# WiFi_Board_R0.net
KiCad netlist of a schematic drawn in EAGLE
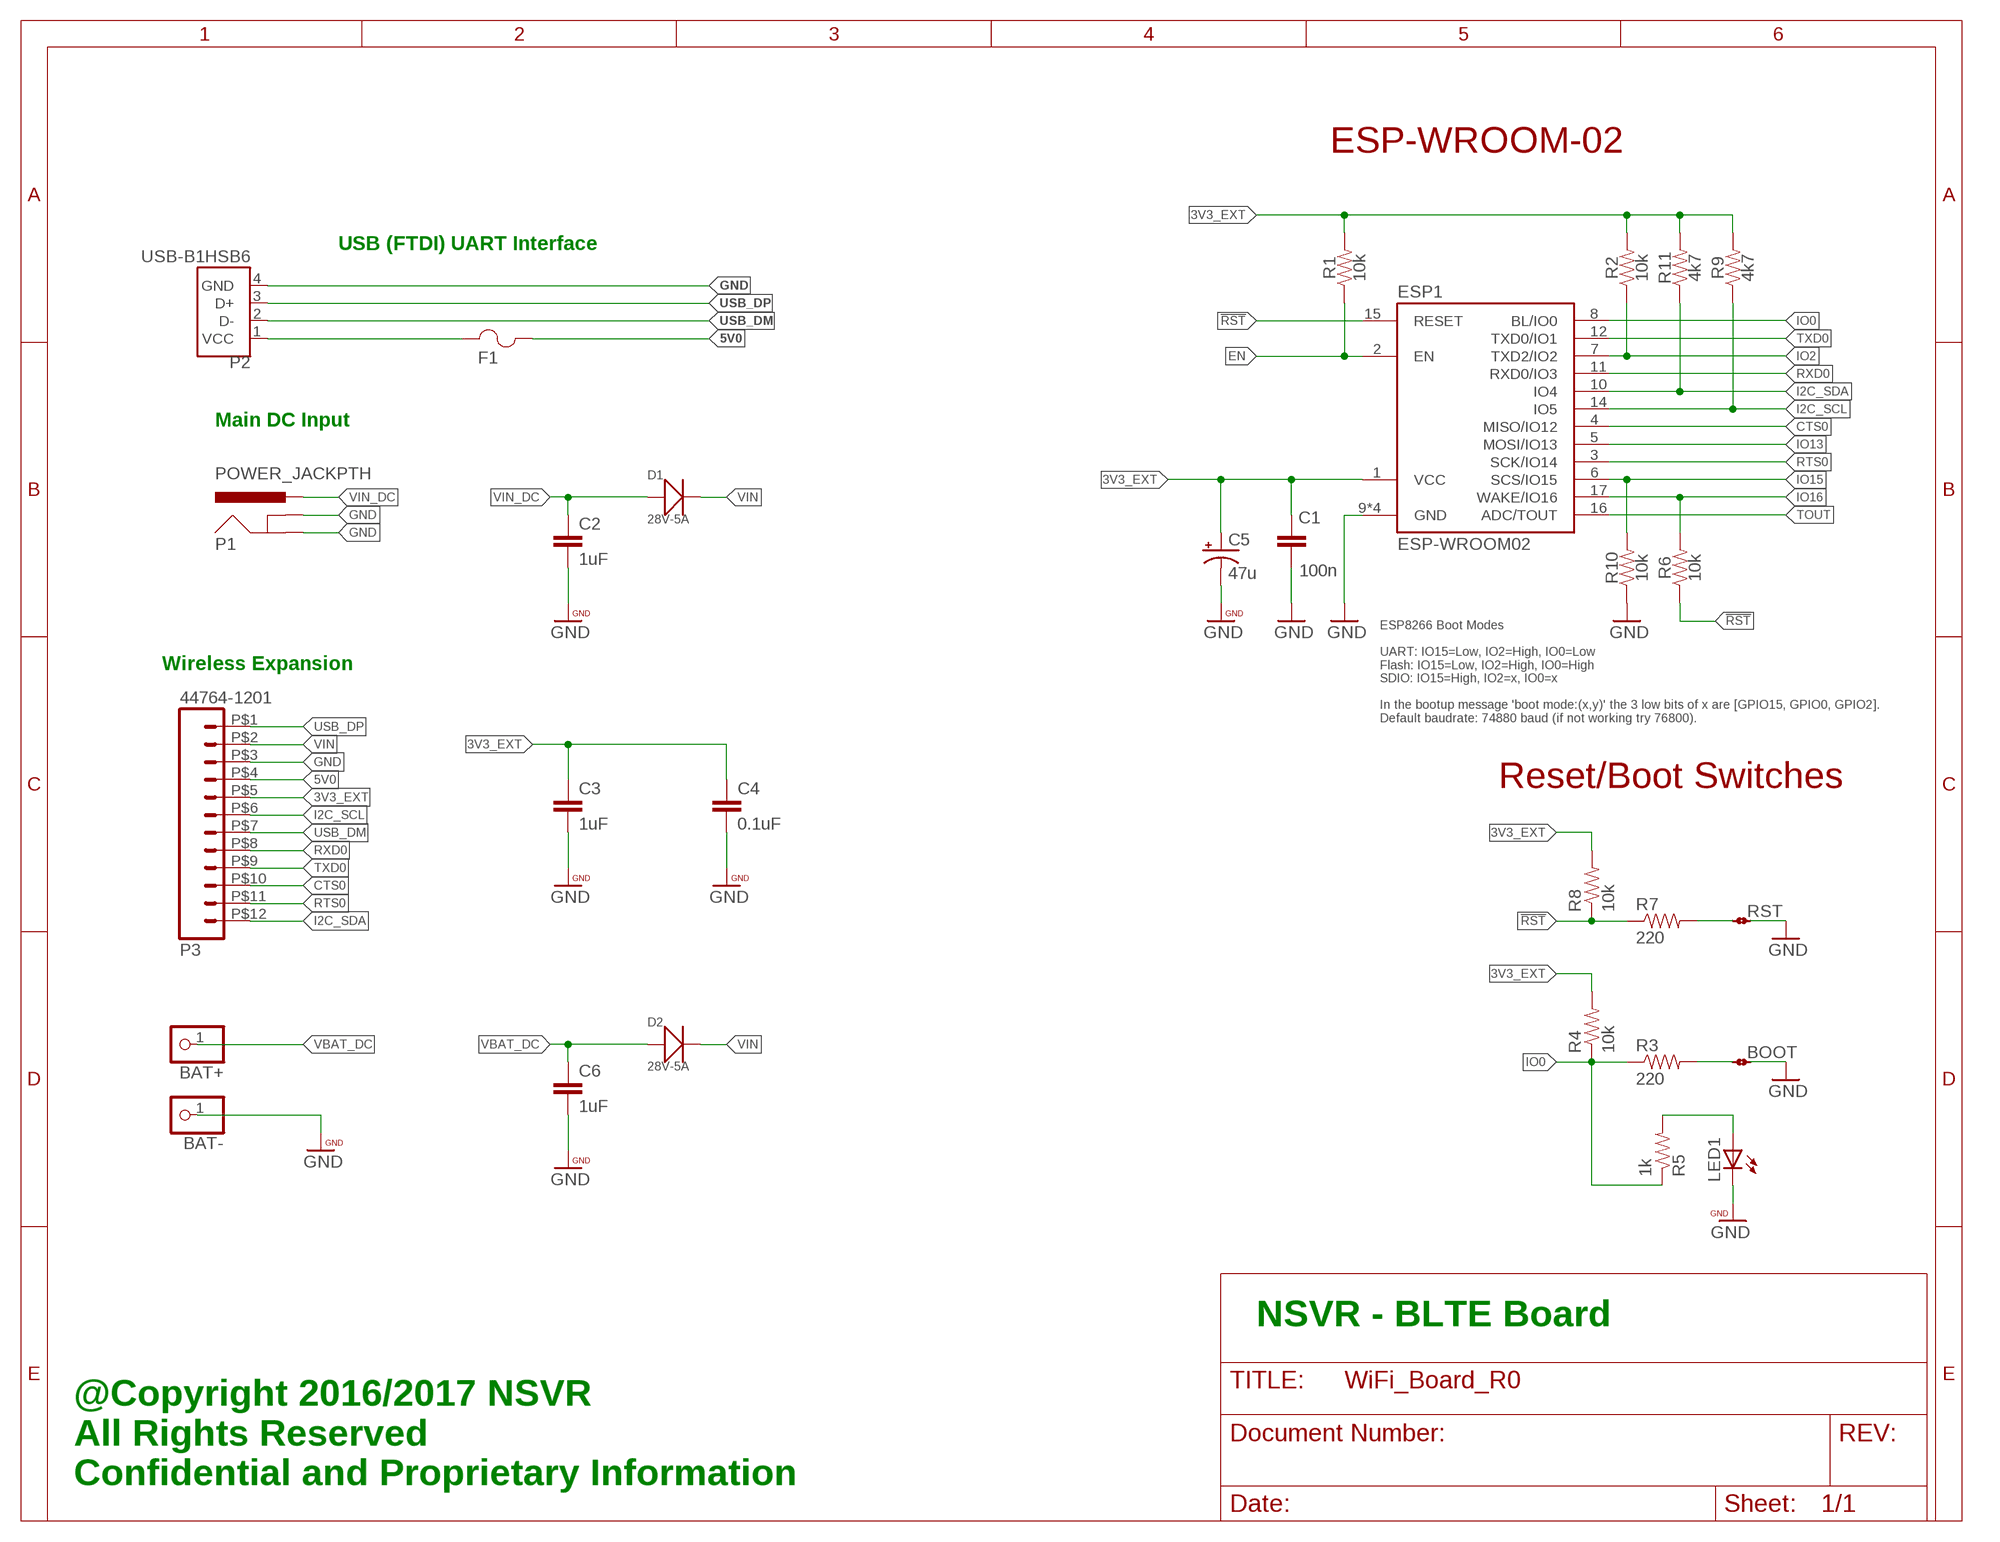
[diagram p0: schematic, sheet 1]

(export (version "E")
  (design (tool "Eeschema 10.0.6"))
  (components
    (comp (ref "BAT+")
      (value "WPAD-1-PTH")
      (footprint "eagle-import:WPAD-1-PTH-2.54")
      (libsource (lib "eagle-import") (part "WPAD-1-PTH"))
    )
    (comp (ref "BAT-")
      (value "WPAD-1-PTH")
      (footprint "eagle-import:WPAD-1-PTH-2.54")
      (libsource (lib "eagle-import") (part "WPAD-1-PTH"))
    )
    (comp (ref "BOOT")
      (value "JMP-2-NO-PTH")
      (footprint "eagle-import:JMP-2-NO-PTH-2.54")
      (libsource (lib "eagle-import") (part "JMP-2-NO-PTH"))
    )
    (comp (ref "C1")
      (value "100n")
      (footprint "eagle-import:0402-CAP")
      (libsource (lib "eagle-import") (part "CAP0402-CAP"))
    )
    (comp (ref "C2")
      (value "1uF")
      (footprint "eagle-import:0402-CAP")
      (libsource (lib "eagle-import") (part "CAP0402-CAP"))
    )
    (comp (ref "C3")
      (value "1uF")
      (footprint "eagle-import:0402-CAP")
      (libsource (lib "eagle-import") (part "CAP0402-CAP"))
    )
    (comp (ref "C4")
      (value "0.1uF")
      (footprint "eagle-import:0402-CAP")
      (libsource (lib "eagle-import") (part "CAP0402-CAP"))
    )
    (comp (ref "C5")
      (value "47u")
      (footprint "eagle-import:PANASONIC_D")
      (libsource (lib "eagle-import") (part "CAP_POLD"))
    )
    (comp (ref "C6")
      (value "1uF")
      (footprint "eagle-import:0402-CAP")
      (libsource (lib "eagle-import") (part "CAP0402-CAP"))
    )
    (comp (ref "D1")
      (value "28V-5A")
      (footprint "eagle-import:DO-214AA")
      (fields (field (name "MPN") "SS54B"))
      (libsource (lib "eagle-import") (part "SMD-DIODE-SCHOTTKY-28V-5A(DO-214AA)"))
    )
    (comp (ref "D2")
      (value "28V-5A")
      (footprint "eagle-import:DO-214AA")
      (fields (field (name "MPN") "SS54B"))
      (libsource (lib "eagle-import") (part "SMD-DIODE-SCHOTTKY-28V-5A(DO-214AA)"))
    )
    (comp (ref "ESP1")
      (value "ESP-WROOM02")
      (footprint "eagle-import:ESP-WROOM02")
      (libsource (lib "eagle-import") (part "ESP-WROOM02"))
    )
    (comp (ref "F1")
      (value "1206L050YR")
      (footprint "eagle-import:1206LSERIES")
      (fields (field (name "COPYRIGHT") "Copyright C 2015 Accelerated Designs. All rights reserved"))
      (libsource (lib "eagle-import") (part "1206L050YR"))
    )
    (comp (ref "LED1")
      (value "LEDCHIP-LED0603")
      (footprint "eagle-import:CHIP-LED0603")
      (libsource (lib "eagle-import") (part "LEDCHIP-LED0603"))
    )
    (comp (ref "P1")
      (value "POWER_JACKPTH")
      (footprint "eagle-import:POWER_JACK_PTH")
      (libsource (lib "eagle-import") (part "POWER_JACKPTH"))
    )
    (comp (ref "P2")
      (value "USB-B1HSB6")
      (footprint "eagle-import:OST_USB-B1HSB6")
      (fields (field (name "MF") "On Shore Technology"))
      (libsource (lib "eagle-import") (part "USB-B1HSB6"))
    )
    (comp (ref "P3")
      (value "44764-1201")
      (footprint "eagle-import:44764-1201")
      (libsource (lib "eagle-import") (part "44764-1201"))
    )
    (comp (ref "R1")
      (value "10k")
      (footprint "eagle-import:EIA-0402")
      (libsource (lib "eagle-import") (part "RESISTOR0402-TYP"))
    )
    (comp (ref "R2")
      (value "10k")
      (footprint "eagle-import:EIA-0402")
      (libsource (lib "eagle-import") (part "RESISTOR0402-TYP"))
    )
    (comp (ref "R3")
      (value "220")
      (footprint "eagle-import:EIA-0402")
      (libsource (lib "eagle-import") (part "RESISTOR0402-TYP"))
    )
    (comp (ref "R4")
      (value "10k")
      (footprint "eagle-import:EIA-0402")
      (libsource (lib "eagle-import") (part "RESISTOR0402-TYP"))
    )
    (comp (ref "R5")
      (value "1k")
      (footprint "eagle-import:EIA-0402")
      (libsource (lib "eagle-import") (part "RESISTOR0402-TYP"))
    )
    (comp (ref "R6")
      (value "10k")
      (footprint "eagle-import:EIA-0402")
      (libsource (lib "eagle-import") (part "RESISTOR0402-TYP"))
    )
    (comp (ref "R7")
      (value "220")
      (footprint "eagle-import:EIA-0402")
      (libsource (lib "eagle-import") (part "RESISTOR0402-TYP"))
    )
    (comp (ref "R8")
      (value "10k")
      (footprint "eagle-import:EIA-0402")
      (libsource (lib "eagle-import") (part "RESISTOR0402-TYP"))
    )
    (comp (ref "R9")
      (value "4k7")
      (footprint "eagle-import:EIA-0402")
      (libsource (lib "eagle-import") (part "RESISTOR0402-TYP"))
    )
    (comp (ref "R10")
      (value "10k")
      (footprint "eagle-import:EIA-0402")
      (libsource (lib "eagle-import") (part "RESISTOR0402-TYP"))
    )
    (comp (ref "R11")
      (value "4k7")
      (footprint "eagle-import:EIA-0402")
      (libsource (lib "eagle-import") (part "RESISTOR0402-TYP"))
    )
    (comp (ref "RST")
      (value "JMP-2-NO-PTH")
      (footprint "eagle-import:JMP-2-NO-PTH-2.54")
      (libsource (lib "eagle-import") (part "JMP-2-NO-PTH"))
    )
  )
  (nets
    (net (code "1") (name "/~{RST}") (class "Default")
      (node (ref "ESP1") (pin "15") (pinfunction "RESET_15") (pintype "bidirectional"))
      (node (ref "R6") (pin "1") (pinfunction "1_1") (pintype "passive"))
      (node (ref "R7") (pin "1") (pinfunction "1_1") (pintype "passive"))
      (node (ref "R8") (pin "1") (pinfunction "1_1") (pintype "passive"))
    )
    (net (code "2") (name "3V3_EXT") (class "Default")
      (node (ref "C1") (pin "2") (pinfunction "2_2") (pintype "passive"))
      (node (ref "C3") (pin "1") (pinfunction "1_1") (pintype "passive"))
      (node (ref "C4") (pin "1") (pinfunction "1_1") (pintype "passive"))
      (node (ref "C5") (pin "+") (pinfunction "+_+") (pintype "passive"))
      (node (ref "ESP1") (pin "1") (pinfunction "VCC_1") (pintype "power_in"))
      (node (ref "P3") (pin "P$5") (pinfunction "5_P$5") (pintype "passive"))
      (node (ref "R1") (pin "2") (pinfunction "2_2") (pintype "passive"))
      (node (ref "R11") (pin "2") (pinfunction "2_2") (pintype "passive"))
      (node (ref "R2") (pin "2") (pinfunction "2_2") (pintype "passive"))
      (node (ref "R4") (pin "2") (pinfunction "2_2") (pintype "passive"))
      (node (ref "R8") (pin "2") (pinfunction "2_2") (pintype "passive"))
      (node (ref "R9") (pin "2") (pinfunction "2_2") (pintype "passive"))
    )
    (net (code "3") (name "5V0") (class "Default")
      (node (ref "F1") (pin "2") (pinfunction "2_2") (pintype "passive"))
      (node (ref "P3") (pin "P$4") (pinfunction "4_P$4") (pintype "passive"))
    )
    (net (code "4") (name "CTS0") (class "Default")
      (node (ref "ESP1") (pin "4") (pinfunction "MISO/IO12_4") (pintype "bidirectional"))
      (node (ref "P3") (pin "P$10") (pinfunction "10_P$10") (pintype "passive"))
    )
    (net (code "5") (name "EN") (class "Default")
      (node (ref "ESP1") (pin "2") (pinfunction "EN_2") (pintype "bidirectional"))
      (node (ref "R1") (pin "1") (pinfunction "1_1") (pintype "passive"))
    )
    (net (code "6") (name "GND") (class "Default")
      (node (ref "BAT-") (pin "1") (pinfunction "1_1") (pintype "passive"))
      (node (ref "BOOT") (pin "2") (pinfunction "2_2") (pintype "passive"))
      (node (ref "C1") (pin "1") (pinfunction "1_1") (pintype "passive"))
      (node (ref "C2") (pin "2") (pinfunction "2_2") (pintype "passive"))
      (node (ref "C3") (pin "2") (pinfunction "2_2") (pintype "passive"))
      (node (ref "C4") (pin "2") (pinfunction "2_2") (pintype "passive"))
      (node (ref "C5") (pin "-") (pinfunction "-_-") (pintype "passive"))
      (node (ref "C6") (pin "2") (pinfunction "2_2") (pintype "passive"))
      (node (ref "ESP1") (pin "13") (pinfunction "GND_13") (pintype "power_in"))
      (node (ref "ESP1") (pin "18") (pinfunction "GND_18") (pintype "power_in"))
      (node (ref "ESP1") (pin "9") (pinfunction "GND_9") (pintype "power_in"))
      (node (ref "ESP1") (pin "TP") (pinfunction "GND_TP") (pintype "power_in"))
      (node (ref "LED1") (pin "C") (pinfunction "C_C") (pintype "passive"))
      (node (ref "P1") (pin "GND") (pinfunction "GND_GND") (pintype "bidirectional"))
      (node (ref "P1") (pin "GNDBREAK") (pinfunction "GNDBREAK_GNDBREAK") (pintype "bidirectional"))
      (node (ref "P2") (pin "4") (pinfunction "GND_4") (pintype "power_in"))
      (node (ref "P3") (pin "P$3") (pinfunction "3_P$3") (pintype "passive"))
      (node (ref "R10") (pin "1") (pinfunction "1_1") (pintype "passive"))
      (node (ref "RST") (pin "2") (pinfunction "2_2") (pintype "passive"))
    )
    (net (code "7") (name "I2C_SCL") (class "Default")
      (node (ref "ESP1") (pin "14") (pinfunction "IO5_14") (pintype "bidirectional"))
      (node (ref "P3") (pin "P$6") (pinfunction "6_P$6") (pintype "passive"))
      (node (ref "R9") (pin "1") (pinfunction "1_1") (pintype "passive"))
    )
    (net (code "8") (name "I2C_SDA") (class "Default")
      (node (ref "ESP1") (pin "10") (pinfunction "IO4_10") (pintype "bidirectional"))
      (node (ref "P3") (pin "P$12") (pinfunction "12_P$12") (pintype "passive"))
      (node (ref "R11") (pin "1") (pinfunction "1_1") (pintype "passive"))
    )
    (net (code "9") (name "IO0") (class "Default")
      (node (ref "ESP1") (pin "8") (pinfunction "BL/IO0_8") (pintype "bidirectional"))
      (node (ref "R3") (pin "1") (pinfunction "1_1") (pintype "passive"))
      (node (ref "R4") (pin "1") (pinfunction "1_1") (pintype "passive"))
      (node (ref "R5") (pin "1") (pinfunction "1_1") (pintype "passive"))
    )
    (net (code "10") (name "IO2") (class "Default")
      (node (ref "ESP1") (pin "7") (pinfunction "TXD2/IO2_7") (pintype "bidirectional"))
      (node (ref "R2") (pin "1") (pinfunction "1_1") (pintype "passive"))
    )
    (net (code "11") (name "IO13") (class "Default")
      (node (ref "ESP1") (pin "5") (pinfunction "MOSI/IO13_5") (pintype "bidirectional"))
    )
    (net (code "12") (name "IO15") (class "Default")
      (node (ref "ESP1") (pin "6") (pinfunction "SCS/IO15_6") (pintype "bidirectional"))
      (node (ref "R10") (pin "2") (pinfunction "2_2") (pintype "passive"))
    )
    (net (code "13") (name "IO16") (class "Default")
      (node (ref "ESP1") (pin "17") (pinfunction "WAKE/IO16_17") (pintype "bidirectional"))
      (node (ref "R6") (pin "2") (pinfunction "2_2") (pintype "passive"))
    )
    (net (code "14") (name "Net-(BOOT-Pad1)") (class "Default")
      (node (ref "BOOT") (pin "1") (pinfunction "1_1") (pintype "passive"))
      (node (ref "R3") (pin "2") (pinfunction "2_2") (pintype "passive"))
    )
    (net (code "15") (name "Net-(LED1-PadA)") (class "Default")
      (node (ref "LED1") (pin "A") (pinfunction "A_A") (pintype "passive"))
      (node (ref "R5") (pin "2") (pinfunction "2_2") (pintype "passive"))
    )
    (net (code "16") (name "Net-(P2-VCC)") (class "Default")
      (node (ref "F1") (pin "1") (pinfunction "1_1") (pintype "passive"))
      (node (ref "P2") (pin "1") (pinfunction "VCC_1") (pintype "power_in"))
    )
    (net (code "17") (name "Net-(R7-Pad2)") (class "Default")
      (node (ref "R7") (pin "2") (pinfunction "2_2") (pintype "passive"))
      (node (ref "RST") (pin "1") (pinfunction "1_1") (pintype "passive"))
    )
    (net (code "18") (name "RTS0") (class "Default")
      (node (ref "ESP1") (pin "3") (pinfunction "SCK/IO14_3") (pintype "bidirectional"))
      (node (ref "P3") (pin "P$11") (pinfunction "11_P$11") (pintype "passive"))
    )
    (net (code "19") (name "RXD0") (class "Default")
      (node (ref "ESP1") (pin "11") (pinfunction "RXD0/IO3_11") (pintype "bidirectional"))
      (node (ref "P3") (pin "P$8") (pinfunction "8_P$8") (pintype "passive"))
    )
    (net (code "20") (name "TOUT") (class "Default")
      (node (ref "ESP1") (pin "16") (pinfunction "ADC/TOUT_16") (pintype "bidirectional"))
    )
    (net (code "21") (name "TXD0") (class "Default")
      (node (ref "ESP1") (pin "12") (pinfunction "TXD0/IO1_12") (pintype "bidirectional"))
      (node (ref "P3") (pin "P$9") (pinfunction "9_P$9") (pintype "passive"))
    )
    (net (code "22") (name "USB_DM") (class "Default")
      (node (ref "P2") (pin "2") (pinfunction "D-_2") (pintype "bidirectional"))
      (node (ref "P3") (pin "P$7") (pinfunction "7_P$7") (pintype "passive"))
    )
    (net (code "23") (name "USB_DP") (class "Default")
      (node (ref "P2") (pin "3") (pinfunction "D+_3") (pintype "bidirectional"))
      (node (ref "P3") (pin "P$1") (pinfunction "1_P$1") (pintype "passive"))
    )
    (net (code "24") (name "VBAT_DC") (class "Default")
      (node (ref "BAT+") (pin "1") (pinfunction "1_1") (pintype "passive"))
      (node (ref "C6") (pin "1") (pinfunction "1_1") (pintype "passive"))
      (node (ref "D2") (pin "+") (pinfunction "+_+") (pintype "passive"))
    )
    (net (code "25") (name "VIN") (class "Default")
      (node (ref "D1") (pin "-") (pinfunction "-_-") (pintype "passive"))
      (node (ref "D2") (pin "-") (pinfunction "-_-") (pintype "passive"))
      (node (ref "P3") (pin "P$2") (pinfunction "2_P$2") (pintype "passive"))
    )
    (net (code "26") (name "VIN_DC") (class "Default")
      (node (ref "C2") (pin "1") (pinfunction "1_1") (pintype "passive"))
      (node (ref "D1") (pin "+") (pinfunction "+_+") (pintype "passive"))
      (node (ref "P1") (pin "PWR") (pinfunction "PWR_PWR") (pintype "bidirectional"))
    )
  )
)
